# Supply.net
KiCad netlist of a schematic drawn in Altium Designer
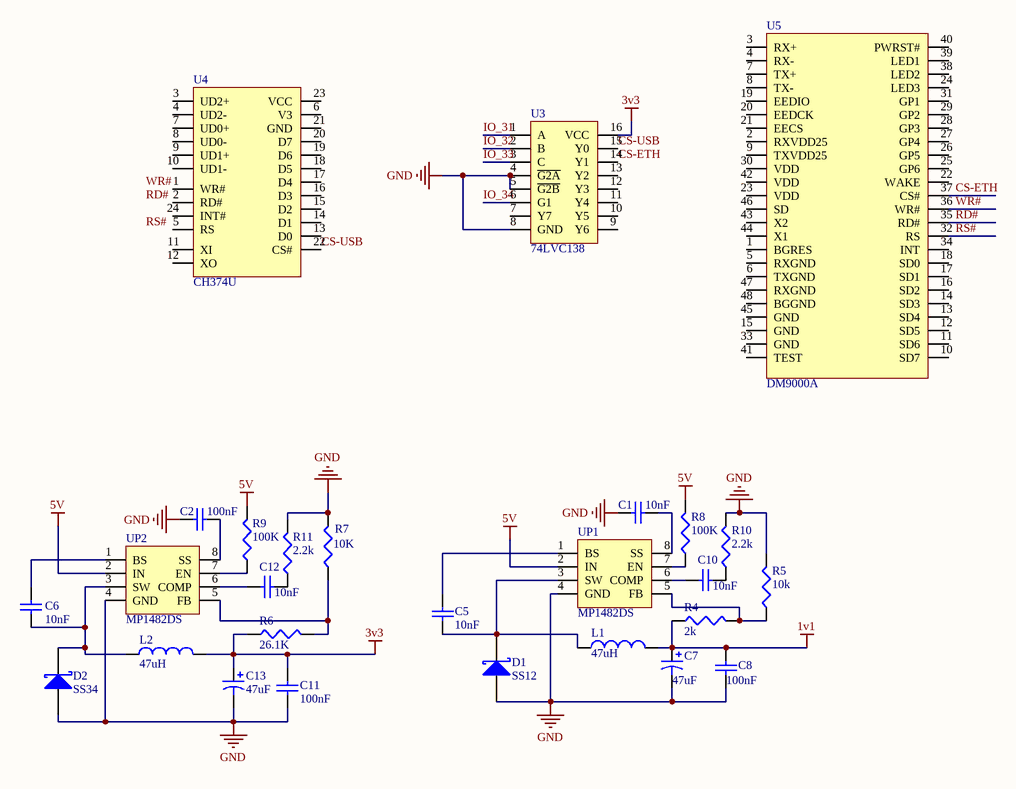
[diagram p0: Supply.SchDoc]

(export (version "E")
  (design (tool "Eeschema 10.0.6"))
  (components
    (comp (ref "C1")
      (value "10nF")
      (footprint "6-0805_M")
      (description "Capacitor")
      (fields (field (name "Comment") "Cap") (field (name "PUBLISHER") "Altium Limited"))
      (libsource (lib "Miscellaneous Devices") (part "Cap"))
    )
    (comp (ref "C2")
      (value "100nF")
      (footprint "6-0805_M")
      (description "Capacitor")
      (fields (field (name "Comment") "Cap") (field (name "PUBLISHER") "Altium Limited"))
      (libsource (lib "Miscellaneous Devices") (part "Cap"))
    )
    (comp (ref "C5")
      (value "10nF")
      (footprint "6-0805_M")
      (description "Capacitor")
      (fields (field (name "Comment") "Cap") (field (name "PUBLISHER") "Altium Limited"))
      (libsource (lib "Miscellaneous Devices") (part "Cap"))
    )
    (comp (ref "C6")
      (value "10nF")
      (footprint "6-0805_M")
      (description "Capacitor")
      (fields (field (name "Comment") "Cap") (field (name "PUBLISHER") "Altium Limited"))
      (libsource (lib "Miscellaneous Devices") (part "Cap"))
    )
    (comp (ref "C7")
      (value "47uF")
      (footprint "TanCap-1210")
      (description "Polarized Capacitor (Surface Mount)")
      (fields (field (name "Comment") "Cap Pol3") (field (name "PUBLISHER") "Altium Limited"))
      (libsource (lib "Miscellaneous Devices") (part "Cap Pol3"))
    )
    (comp (ref "C8")
      (value "100nF")
      (footprint "6-0805_M")
      (description "Capacitor")
      (fields (field (name "Comment") "Cap") (field (name "PUBLISHER") "Altium Limited"))
      (libsource (lib "Miscellaneous Devices") (part "Cap"))
    )
    (comp (ref "C10")
      (value "10nF")
      (footprint "6-0805_M")
      (description "Capacitor")
      (fields (field (name "Comment") "Cap") (field (name "PUBLISHER") "Altium Limited"))
      (libsource (lib "Miscellaneous Devices") (part "Cap"))
    )
    (comp (ref "C11")
      (value "100nF")
      (footprint "6-0805_M")
      (description "Capacitor")
      (fields (field (name "Comment") "Cap") (field (name "PUBLISHER") "Altium Limited"))
      (libsource (lib "Miscellaneous Devices") (part "Cap"))
    )
    (comp (ref "C12")
      (value "10nF")
      (footprint "6-0805_M")
      (description "Capacitor")
      (fields (field (name "Comment") "Cap") (field (name "PUBLISHER") "Altium Limited"))
      (libsource (lib "Miscellaneous Devices") (part "Cap"))
    )
    (comp (ref "C13")
      (value "47uF")
      (footprint "TanCap-1210")
      (description "Polarized Capacitor (Surface Mount)")
      (fields (field (name "Comment") "Cap Pol3") (field (name "PUBLISHER") "Altium Limited"))
      (libsource (lib "Miscellaneous Devices") (part "Cap Pol3"))
    )
    (comp (ref "D1")
      (value "SS12")
      (footprint "SMB")
      (description "Schottky Diode")
      (fields (field (name "PUBLISHER") "Altium Limited"))
      (libsource (lib "Miscellaneous Devices") (part "D Schottky"))
    )
    (comp (ref "D2")
      (value "SS34")
      (footprint "SMB")
      (description "Schottky Diode")
      (fields (field (name "PUBLISHER") "Altium Limited"))
      (libsource (lib "Miscellaneous Devices") (part "D Schottky"))
    )
    (comp (ref "L1")
      (value "47uH")
      (footprint "PIND2020")
      (description "Inductor")
      (fields (field (name "PUBLISHER") "Altium Limited"))
      (libsource (lib "Miscellaneous Devices") (part "Inductor"))
    )
    (comp (ref "L2")
      (value "47uH")
      (footprint "PIND2020")
      (description "Inductor")
      (fields (field (name "PUBLISHER") "Altium Limited"))
      (libsource (lib "Miscellaneous Devices") (part "Inductor"))
    )
    (comp (ref "R4")
      (value "2k")
      (footprint "6-0805_M")
      (description "Resistor")
      (fields (field (name "Comment") "Res3") (field (name "PUBLISHER") "Altium Limited"))
      (libsource (lib "Miscellaneous Devices") (part "Res3"))
    )
    (comp (ref "R5")
      (value "10k")
      (footprint "6-0805_M")
      (description "Resistor")
      (fields (field (name "Comment") "Res3") (field (name "PUBLISHER") "Altium Limited"))
      (libsource (lib "Miscellaneous Devices") (part "Res3"))
    )
    (comp (ref "R6")
      (value "26.1K")
      (footprint "6-0805_M")
      (description "Resistor")
      (fields (field (name "Comment") "Res3") (field (name "PUBLISHER") "Altium Limited"))
      (libsource (lib "Miscellaneous Devices") (part "Res3"))
    )
    (comp (ref "R7")
      (value "10K")
      (footprint "6-0805_M")
      (description "Resistor")
      (fields (field (name "Comment") "Res3") (field (name "PUBLISHER") "Altium Limited"))
      (libsource (lib "Miscellaneous Devices") (part "Res3"))
    )
    (comp (ref "R8")
      (value "100K")
      (footprint "6-0805_M")
      (description "Resistor")
      (fields (field (name "Comment") "Res3") (field (name "PUBLISHER") "Altium Limited"))
      (libsource (lib "Miscellaneous Devices") (part "Res3"))
    )
    (comp (ref "R9")
      (value "100K")
      (footprint "6-0805_M")
      (description "Resistor")
      (fields (field (name "Comment") "Res3") (field (name "PUBLISHER") "Altium Limited"))
      (libsource (lib "Miscellaneous Devices") (part "Res3"))
    )
    (comp (ref "R10")
      (value "2.2k")
      (footprint "6-0805_M")
      (description "Resistor")
      (fields (field (name "Comment") "Res3") (field (name "PUBLISHER") "Altium Limited"))
      (libsource (lib "Miscellaneous Devices") (part "Res3"))
    )
    (comp (ref "R11")
      (value "2.2k")
      (footprint "6-0805_M")
      (description "Resistor")
      (fields (field (name "Comment") "Res3") (field (name "PUBLISHER") "Altium Limited"))
      (libsource (lib "Miscellaneous Devices") (part "Res3"))
    )
    (comp (ref "U3") (value "74LVC138") (libsource (lib "74xLogic") (part "74x138")))
    (comp (ref "U4") (value "CH374U") (libsource (lib "WCH_Chips") (part "CH374U")))
    (comp (ref "U5") (value "DM9000A") (libsource (lib "ETH_Solution") (part "DM9000A")))
    (comp (ref "UP1")
      (value "MP1482DS")
      (footprint "SOP8N-127P600X200")
      (libsource (lib "PowerChips") (part "MP1482DS"))
    )
    (comp (ref "UP2")
      (value "MP1482DS")
      (footprint "SOP8N-127P600X200")
      (libsource (lib "PowerChips") (part "MP1482DS"))
    )
  )
  (nets
    (net (code "1") (name "/CS-ETH") (class "Default")
      (node (ref "U3") (pin "14") (pinfunction "Y1_14") (pintype "passive"))
      (node (ref "U5") (pin "37") (pinfunction "CS#_37") (pintype "passive"))
    )
    (net (code "2") (name "/CS-USB") (class "Default")
      (node (ref "U3") (pin "15") (pinfunction "Y0_15") (pintype "passive"))
      (node (ref "U4") (pin "22") (pinfunction "CS#_22") (pintype "passive"))
    )
    (net (code "3") (name "/IO_31") (class "Default")
      (node (ref "U3") (pin "1") (pinfunction "A_1") (pintype "passive"))
    )
    (net (code "4") (name "/IO_32") (class "Default")
      (node (ref "U3") (pin "2") (pinfunction "B_2") (pintype "passive"))
    )
    (net (code "5") (name "/IO_33") (class "Default")
      (node (ref "U3") (pin "3") (pinfunction "C_3") (pintype "passive"))
    )
    (net (code "6") (name "/IO_34") (class "Default")
      (node (ref "U3") (pin "6") (pinfunction "G1_6") (pintype "passive"))
    )
    (net (code "7") (name "/RD#") (class "Default")
      (node (ref "U5") (pin "35") (pinfunction "RD#_35") (pintype "passive"))
    )
    (net (code "8") (name "/RS#") (class "Default")
      (node (ref "U5") (pin "32") (pinfunction "RS_32") (pintype "passive"))
    )
    (net (code "9") (name "/WR#") (class "Default")
      (node (ref "U5") (pin "36") (pinfunction "WR#_36") (pintype "passive"))
    )
    (net (code "10") (name "1v1") (class "Default")
      (node (ref "C7") (pin "1") (pinfunction "1_1") (pintype "passive"))
      (node (ref "C8") (pin "2") (pinfunction "2_2") (pintype "passive"))
      (node (ref "L1") (pin "2") (pinfunction "2_2") (pintype "passive"))
      (node (ref "R4") (pin "1") (pinfunction "1_1") (pintype "passive"))
    )
    (net (code "11") (name "3v3") (class "Default")
      (node (ref "C11") (pin "2") (pinfunction "2_2") (pintype "passive"))
      (node (ref "C13") (pin "1") (pinfunction "1_1") (pintype "passive"))
      (node (ref "L2") (pin "2") (pinfunction "2_2") (pintype "passive"))
      (node (ref "R6") (pin "1") (pinfunction "1_1") (pintype "passive"))
      (node (ref "U3") (pin "16") (pinfunction "VCC_16") (pintype "passive"))
    )
    (net (code "12") (name "5V") (class "Default")
      (node (ref "R8") (pin "2") (pinfunction "2_2") (pintype "passive"))
      (node (ref "R9") (pin "2") (pinfunction "2_2") (pintype "passive"))
      (node (ref "UP1") (pin "2") (pinfunction "IN_2") (pintype "passive"))
      (node (ref "UP2") (pin "2") (pinfunction "IN_2") (pintype "passive"))
    )
    (net (code "13") (name "GND") (class "Default")
      (node (ref "C1") (pin "1") (pinfunction "1_1") (pintype "passive"))
      (node (ref "C11") (pin "1") (pinfunction "1_1") (pintype "passive"))
      (node (ref "C13") (pin "2") (pinfunction "2_2") (pintype "passive"))
      (node (ref "C2") (pin "1") (pinfunction "1_1") (pintype "passive"))
      (node (ref "C7") (pin "2") (pinfunction "2_2") (pintype "passive"))
      (node (ref "C8") (pin "1") (pinfunction "1_1") (pintype "passive"))
      (node (ref "D1") (pin "1") (pinfunction "A_1") (pintype "passive"))
      (node (ref "D2") (pin "1") (pinfunction "A_1") (pintype "passive"))
      (node (ref "R10") (pin "2") (pinfunction "2_2") (pintype "passive"))
      (node (ref "R11") (pin "2") (pinfunction "2_2") (pintype "passive"))
      (node (ref "R5") (pin "2") (pinfunction "2_2") (pintype "passive"))
      (node (ref "R7") (pin "2") (pinfunction "2_2") (pintype "passive"))
      (node (ref "U3") (pin "4") (pinfunction "~{G2A}_4") (pintype "passive"))
      (node (ref "U3") (pin "5") (pinfunction "~{G2B}_5") (pintype "passive"))
      (node (ref "U3") (pin "8") (pinfunction "GND_8") (pintype "passive"))
      (node (ref "UP1") (pin "4") (pinfunction "GND_4") (pintype "passive"))
      (node (ref "UP2") (pin "4") (pinfunction "GND_4") (pintype "passive"))
    )
    (net (code "14") (name "Net-(C10-Pad2)") (class "Default")
      (node (ref "C10") (pin "2") (pinfunction "2_2") (pintype "passive"))
      (node (ref "R10") (pin "1") (pinfunction "1_1") (pintype "passive"))
    )
    (net (code "15") (name "Net-(C12-Pad2)") (class "Default")
      (node (ref "C12") (pin "2") (pinfunction "2_2") (pintype "passive"))
      (node (ref "R11") (pin "1") (pinfunction "1_1") (pintype "passive"))
    )
    (net (code "16") (name "Net-(D1-K)") (class "Default")
      (node (ref "C5") (pin "1") (pinfunction "1_1") (pintype "passive"))
      (node (ref "D1") (pin "2") (pinfunction "K_2") (pintype "passive"))
      (node (ref "L1") (pin "1") (pinfunction "1_1") (pintype "passive"))
      (node (ref "UP1") (pin "3") (pinfunction "SW_3") (pintype "passive"))
    )
    (net (code "17") (name "Net-(D2-K)") (class "Default")
      (node (ref "C6") (pin "1") (pinfunction "1_1") (pintype "passive"))
      (node (ref "D2") (pin "2") (pinfunction "K_2") (pintype "passive"))
      (node (ref "L2") (pin "1") (pinfunction "1_1") (pintype "passive"))
      (node (ref "UP2") (pin "3") (pinfunction "SW_3") (pintype "passive"))
    )
    (net (code "18") (name "Net-(UP1-BS)") (class "Default")
      (node (ref "C5") (pin "2") (pinfunction "2_2") (pintype "passive"))
      (node (ref "UP1") (pin "1") (pinfunction "BS_1") (pintype "passive"))
    )
    (net (code "19") (name "Net-(UP1-COMP)") (class "Default")
      (node (ref "C10") (pin "1") (pinfunction "1_1") (pintype "passive"))
      (node (ref "UP1") (pin "6") (pinfunction "COMP_6") (pintype "passive"))
    )
    (net (code "20") (name "Net-(UP1-EN)") (class "Default")
      (node (ref "R8") (pin "1") (pinfunction "1_1") (pintype "passive"))
      (node (ref "UP1") (pin "7") (pinfunction "EN_7") (pintype "passive"))
    )
    (net (code "21") (name "Net-(UP1-FB)") (class "Default")
      (node (ref "R4") (pin "2") (pinfunction "2_2") (pintype "passive"))
      (node (ref "R5") (pin "1") (pinfunction "1_1") (pintype "passive"))
      (node (ref "UP1") (pin "5") (pinfunction "FB_5") (pintype "passive"))
    )
    (net (code "22") (name "Net-(UP1-SS)") (class "Default")
      (node (ref "C1") (pin "2") (pinfunction "2_2") (pintype "passive"))
      (node (ref "UP1") (pin "8") (pinfunction "SS_8") (pintype "passive"))
    )
    (net (code "23") (name "Net-(UP2-BS)") (class "Default")
      (node (ref "C6") (pin "2") (pinfunction "2_2") (pintype "passive"))
      (node (ref "UP2") (pin "1") (pinfunction "BS_1") (pintype "passive"))
    )
    (net (code "24") (name "Net-(UP2-COMP)") (class "Default")
      (node (ref "C12") (pin "1") (pinfunction "1_1") (pintype "passive"))
      (node (ref "UP2") (pin "6") (pinfunction "COMP_6") (pintype "passive"))
    )
    (net (code "25") (name "Net-(UP2-EN)") (class "Default")
      (node (ref "R9") (pin "1") (pinfunction "1_1") (pintype "passive"))
      (node (ref "UP2") (pin "7") (pinfunction "EN_7") (pintype "passive"))
    )
    (net (code "26") (name "Net-(UP2-FB)") (class "Default")
      (node (ref "R6") (pin "2") (pinfunction "2_2") (pintype "passive"))
      (node (ref "R7") (pin "1") (pinfunction "1_1") (pintype "passive"))
      (node (ref "UP2") (pin "5") (pinfunction "FB_5") (pintype "passive"))
    )
    (net (code "27") (name "Net-(UP2-SS)") (class "Default")
      (node (ref "C2") (pin "2") (pinfunction "2_2") (pintype "passive"))
      (node (ref "UP2") (pin "8") (pinfunction "SS_8") (pintype "passive"))
    )
    (net (code "28") (name "unconnected-(U3-Y2-Pad13)") (class "Default")
      (node (ref "U3") (pin "13") (pinfunction "Y2_13") (pintype "passive"))
    )
    (net (code "29") (name "unconnected-(U3-Y3-Pad12)") (class "Default")
      (node (ref "U3") (pin "12") (pinfunction "Y3_12") (pintype "passive"))
    )
    (net (code "30") (name "unconnected-(U3-Y4-Pad11)") (class "Default")
      (node (ref "U3") (pin "11") (pinfunction "Y4_11") (pintype "passive"))
    )
    (net (code "31") (name "unconnected-(U3-Y5-Pad10)") (class "Default")
      (node (ref "U3") (pin "10") (pinfunction "Y5_10") (pintype "passive"))
    )
    (net (code "32") (name "unconnected-(U3-Y6-Pad9)") (class "Default")
      (node (ref "U3") (pin "9") (pinfunction "Y6_9") (pintype "passive"))
    )
    (net (code "33") (name "unconnected-(U3-Y7-Pad7)") (class "Default")
      (node (ref "U3") (pin "7") (pinfunction "Y7_7") (pintype "passive"))
    )
    (net (code "34") (name "unconnected-(U4-D0-Pad13)") (class "Default")
      (node (ref "U4") (pin "13") (pinfunction "D0_13") (pintype "passive"))
    )
    (net (code "35") (name "unconnected-(U4-D1-Pad14)") (class "Default")
      (node (ref "U4") (pin "14") (pinfunction "D1_14") (pintype "passive"))
    )
    (net (code "36") (name "unconnected-(U4-D2-Pad15)") (class "Default")
      (node (ref "U4") (pin "15") (pinfunction "D2_15") (pintype "passive"))
    )
    (net (code "37") (name "unconnected-(U4-D3-Pad16)") (class "Default")
      (node (ref "U4") (pin "16") (pinfunction "D3_16") (pintype "passive"))
    )
    (net (code "38") (name "unconnected-(U4-D4-Pad17)") (class "Default")
      (node (ref "U4") (pin "17") (pinfunction "D4_17") (pintype "passive"))
    )
    (net (code "39") (name "unconnected-(U4-D5-Pad18)") (class "Default")
      (node (ref "U4") (pin "18") (pinfunction "D5_18") (pintype "passive"))
    )
    (net (code "40") (name "unconnected-(U4-D6-Pad19)") (class "Default")
      (node (ref "U4") (pin "19") (pinfunction "D6_19") (pintype "passive"))
    )
    (net (code "41") (name "unconnected-(U4-D7-Pad20)") (class "Default")
      (node (ref "U4") (pin "20") (pinfunction "D7_20") (pintype "passive"))
    )
    (net (code "42") (name "unconnected-(U4-GND-Pad21)") (class "Default")
      (node (ref "U4") (pin "21") (pinfunction "GND_21") (pintype "passive"))
    )
    (net (code "43") (name "unconnected-(U4-INT#-Pad24)") (class "Default")
      (node (ref "U4") (pin "24") (pinfunction "INT#_24") (pintype "passive"))
    )
    (net (code "44") (name "unconnected-(U4-RD#-Pad2)") (class "Default")
      (node (ref "U4") (pin "2") (pinfunction "RD#_2") (pintype "passive"))
    )
    (net (code "45") (name "unconnected-(U4-RS-Pad5)") (class "Default")
      (node (ref "U4") (pin "5") (pinfunction "RS_5") (pintype "passive"))
    )
    (net (code "46") (name "unconnected-(U4-UD0+-Pad7)") (class "Default")
      (node (ref "U4") (pin "7") (pinfunction "UD0+_7") (pintype "passive"))
    )
    (net (code "47") (name "unconnected-(U4-UD0--Pad8)") (class "Default")
      (node (ref "U4") (pin "8") (pinfunction "UD0-_8") (pintype "passive"))
    )
    (net (code "48") (name "unconnected-(U4-UD1+-Pad9)") (class "Default")
      (node (ref "U4") (pin "9") (pinfunction "UD1+_9") (pintype "passive"))
    )
    (net (code "49") (name "unconnected-(U4-UD1--Pad10)") (class "Default")
      (node (ref "U4") (pin "10") (pinfunction "UD1-_10") (pintype "passive"))
    )
    (net (code "50") (name "unconnected-(U4-UD2+-Pad3)") (class "Default")
      (node (ref "U4") (pin "3") (pinfunction "UD2+_3") (pintype "passive"))
    )
    (net (code "51") (name "unconnected-(U4-UD2--Pad4)") (class "Default")
      (node (ref "U4") (pin "4") (pinfunction "UD2-_4") (pintype "passive"))
    )
    (net (code "52") (name "unconnected-(U4-V3-Pad6)") (class "Default")
      (node (ref "U4") (pin "6") (pinfunction "V3_6") (pintype "passive"))
    )
    (net (code "53") (name "unconnected-(U4-VCC-Pad23)") (class "Default")
      (node (ref "U4") (pin "23") (pinfunction "VCC_23") (pintype "passive"))
    )
    (net (code "54") (name "unconnected-(U4-WR#-Pad1)") (class "Default")
      (node (ref "U4") (pin "1") (pinfunction "WR#_1") (pintype "passive"))
    )
    (net (code "55") (name "unconnected-(U4-XI-Pad11)") (class "Default")
      (node (ref "U4") (pin "11") (pinfunction "XI_11") (pintype "passive"))
    )
    (net (code "56") (name "unconnected-(U4-XO-Pad12)") (class "Default")
      (node (ref "U4") (pin "12") (pinfunction "XO_12") (pintype "passive"))
    )
    (net (code "57") (name "unconnected-(U5-BGGND-Pad48)") (class "Default")
      (node (ref "U5") (pin "48") (pinfunction "BGGND_48") (pintype "passive"))
    )
    (net (code "58") (name "unconnected-(U5-BGRES-Pad1)") (class "Default")
      (node (ref "U5") (pin "1") (pinfunction "BGRES_1") (pintype "passive"))
    )
    (net (code "59") (name "unconnected-(U5-EECS-Pad21)") (class "Default")
      (node (ref "U5") (pin "21") (pinfunction "EECS_21") (pintype "passive"))
    )
    (net (code "60") (name "unconnected-(U5-EEDCK-Pad20)") (class "Default")
      (node (ref "U5") (pin "20") (pinfunction "EEDCK_20") (pintype "passive"))
    )
    (net (code "61") (name "unconnected-(U5-EEDIO-Pad19)") (class "Default")
      (node (ref "U5") (pin "19") (pinfunction "EEDIO_19") (pintype "passive"))
    )
    (net (code "62") (name "unconnected-(U5-GND-Pad15)") (class "Default")
      (node (ref "U5") (pin "15") (pinfunction "GND_15") (pintype "passive"))
    )
    (net (code "63") (name "unconnected-(U5-GND-Pad33)") (class "Default")
      (node (ref "U5") (pin "33") (pinfunction "GND_33") (pintype "passive"))
    )
    (net (code "64") (name "unconnected-(U5-GND-Pad45)") (class "Default")
      (node (ref "U5") (pin "45") (pinfunction "GND_45") (pintype "passive"))
    )
    (net (code "65") (name "unconnected-(U5-GP1-Pad31)") (class "Default")
      (node (ref "U5") (pin "31") (pinfunction "GP1_31") (pintype "passive"))
    )
    (net (code "66") (name "unconnected-(U5-GP2-Pad29)") (class "Default")
      (node (ref "U5") (pin "29") (pinfunction "GP2_29") (pintype "passive"))
    )
    (net (code "67") (name "unconnected-(U5-GP3-Pad28)") (class "Default")
      (node (ref "U5") (pin "28") (pinfunction "GP3_28") (pintype "passive"))
    )
    (net (code "68") (name "unconnected-(U5-GP4-Pad27)") (class "Default")
      (node (ref "U5") (pin "27") (pinfunction "GP4_27") (pintype "passive"))
    )
    (net (code "69") (name "unconnected-(U5-GP5-Pad26)") (class "Default")
      (node (ref "U5") (pin "26") (pinfunction "GP5_26") (pintype "passive"))
    )
    (net (code "70") (name "unconnected-(U5-GP6-Pad25)") (class "Default")
      (node (ref "U5") (pin "25") (pinfunction "GP6_25") (pintype "passive"))
    )
    (net (code "71") (name "unconnected-(U5-INT-Pad34)") (class "Default")
      (node (ref "U5") (pin "34") (pinfunction "INT_34") (pintype "passive"))
    )
    (net (code "72") (name "unconnected-(U5-LED1-Pad39)") (class "Default")
      (node (ref "U5") (pin "39") (pinfunction "LED1_39") (pintype "passive"))
    )
    (net (code "73") (name "unconnected-(U5-LED2-Pad38)") (class "Default")
      (node (ref "U5") (pin "38") (pinfunction "LED2_38") (pintype "passive"))
    )
    (net (code "74") (name "unconnected-(U5-LED3-Pad24)") (class "Default")
      (node (ref "U5") (pin "24") (pinfunction "LED3_24") (pintype "passive"))
    )
    (net (code "75") (name "unconnected-(U5-PWRST#-Pad40)") (class "Default")
      (node (ref "U5") (pin "40") (pinfunction "PWRST#_40") (pintype "passive"))
    )
    (net (code "76") (name "unconnected-(U5-RX+-Pad3)") (class "Default")
      (node (ref "U5") (pin "3") (pinfunction "RX+_3") (pintype "passive"))
    )
    (net (code "77") (name "unconnected-(U5-RX--Pad4)") (class "Default")
      (node (ref "U5") (pin "4") (pinfunction "RX-_4") (pintype "passive"))
    )
    (net (code "78") (name "unconnected-(U5-RXGND-Pad5)") (class "Default")
      (node (ref "U5") (pin "5") (pinfunction "RXGND_5") (pintype "passive"))
    )
    (net (code "79") (name "unconnected-(U5-RXGND-Pad47)") (class "Default")
      (node (ref "U5") (pin "47") (pinfunction "RXGND_47") (pintype "passive"))
    )
    (net (code "80") (name "unconnected-(U5-RXVDD25-Pad2)") (class "Default")
      (node (ref "U5") (pin "2") (pinfunction "RXVDD25_2") (pintype "passive"))
    )
    (net (code "81") (name "unconnected-(U5-SD-Pad46)") (class "Default")
      (node (ref "U5") (pin "46") (pinfunction "SD_46") (pintype "passive"))
    )
    (net (code "82") (name "unconnected-(U5-SD0-Pad18)") (class "Default")
      (node (ref "U5") (pin "18") (pinfunction "SD0_18") (pintype "passive"))
    )
    (net (code "83") (name "unconnected-(U5-SD1-Pad17)") (class "Default")
      (node (ref "U5") (pin "17") (pinfunction "SD1_17") (pintype "passive"))
    )
    (net (code "84") (name "unconnected-(U5-SD2-Pad16)") (class "Default")
      (node (ref "U5") (pin "16") (pinfunction "SD2_16") (pintype "passive"))
    )
    (net (code "85") (name "unconnected-(U5-SD3-Pad14)") (class "Default")
      (node (ref "U5") (pin "14") (pinfunction "SD3_14") (pintype "passive"))
    )
    (net (code "86") (name "unconnected-(U5-SD4-Pad13)") (class "Default")
      (node (ref "U5") (pin "13") (pinfunction "SD4_13") (pintype "passive"))
    )
    (net (code "87") (name "unconnected-(U5-SD5-Pad12)") (class "Default")
      (node (ref "U5") (pin "12") (pinfunction "SD5_12") (pintype "passive"))
    )
    (net (code "88") (name "unconnected-(U5-SD6-Pad11)") (class "Default")
      (node (ref "U5") (pin "11") (pinfunction "SD6_11") (pintype "passive"))
    )
    (net (code "89") (name "unconnected-(U5-SD7-Pad10)") (class "Default")
      (node (ref "U5") (pin "10") (pinfunction "SD7_10") (pintype "passive"))
    )
    (net (code "90") (name "unconnected-(U5-TEST-Pad41)") (class "Default")
      (node (ref "U5") (pin "41") (pinfunction "TEST_41") (pintype "passive"))
    )
    (net (code "91") (name "unconnected-(U5-TX+-Pad7)") (class "Default")
      (node (ref "U5") (pin "7") (pinfunction "TX+_7") (pintype "passive"))
    )
    (net (code "92") (name "unconnected-(U5-TX--Pad8)") (class "Default")
      (node (ref "U5") (pin "8") (pinfunction "TX-_8") (pintype "passive"))
    )
    (net (code "93") (name "unconnected-(U5-TXGND-Pad6)") (class "Default")
      (node (ref "U5") (pin "6") (pinfunction "TXGND_6") (pintype "passive"))
    )
    (net (code "94") (name "unconnected-(U5-TXVDD25-Pad9)") (class "Default")
      (node (ref "U5") (pin "9") (pinfunction "TXVDD25_9") (pintype "passive"))
    )
    (net (code "95") (name "unconnected-(U5-VDD-Pad23)") (class "Default")
      (node (ref "U5") (pin "23") (pinfunction "VDD_23") (pintype "passive"))
    )
    (net (code "96") (name "unconnected-(U5-VDD-Pad30)") (class "Default")
      (node (ref "U5") (pin "30") (pinfunction "VDD_30") (pintype "passive"))
    )
    (net (code "97") (name "unconnected-(U5-VDD-Pad42)") (class "Default")
      (node (ref "U5") (pin "42") (pinfunction "VDD_42") (pintype "passive"))
    )
    (net (code "98") (name "unconnected-(U5-WAKE-Pad22)") (class "Default")
      (node (ref "U5") (pin "22") (pinfunction "WAKE_22") (pintype "passive"))
    )
    (net (code "99") (name "unconnected-(U5-X1-Pad44)") (class "Default")
      (node (ref "U5") (pin "44") (pinfunction "X1_44") (pintype "passive"))
    )
    (net (code "100") (name "unconnected-(U5-X2-Pad43)") (class "Default")
      (node (ref "U5") (pin "43") (pinfunction "X2_43") (pintype "passive"))
    )
  )
)
